# ETH_ICD_CCU_HAS.net
KiCad netlist of a schematic drawn in Altium Designer
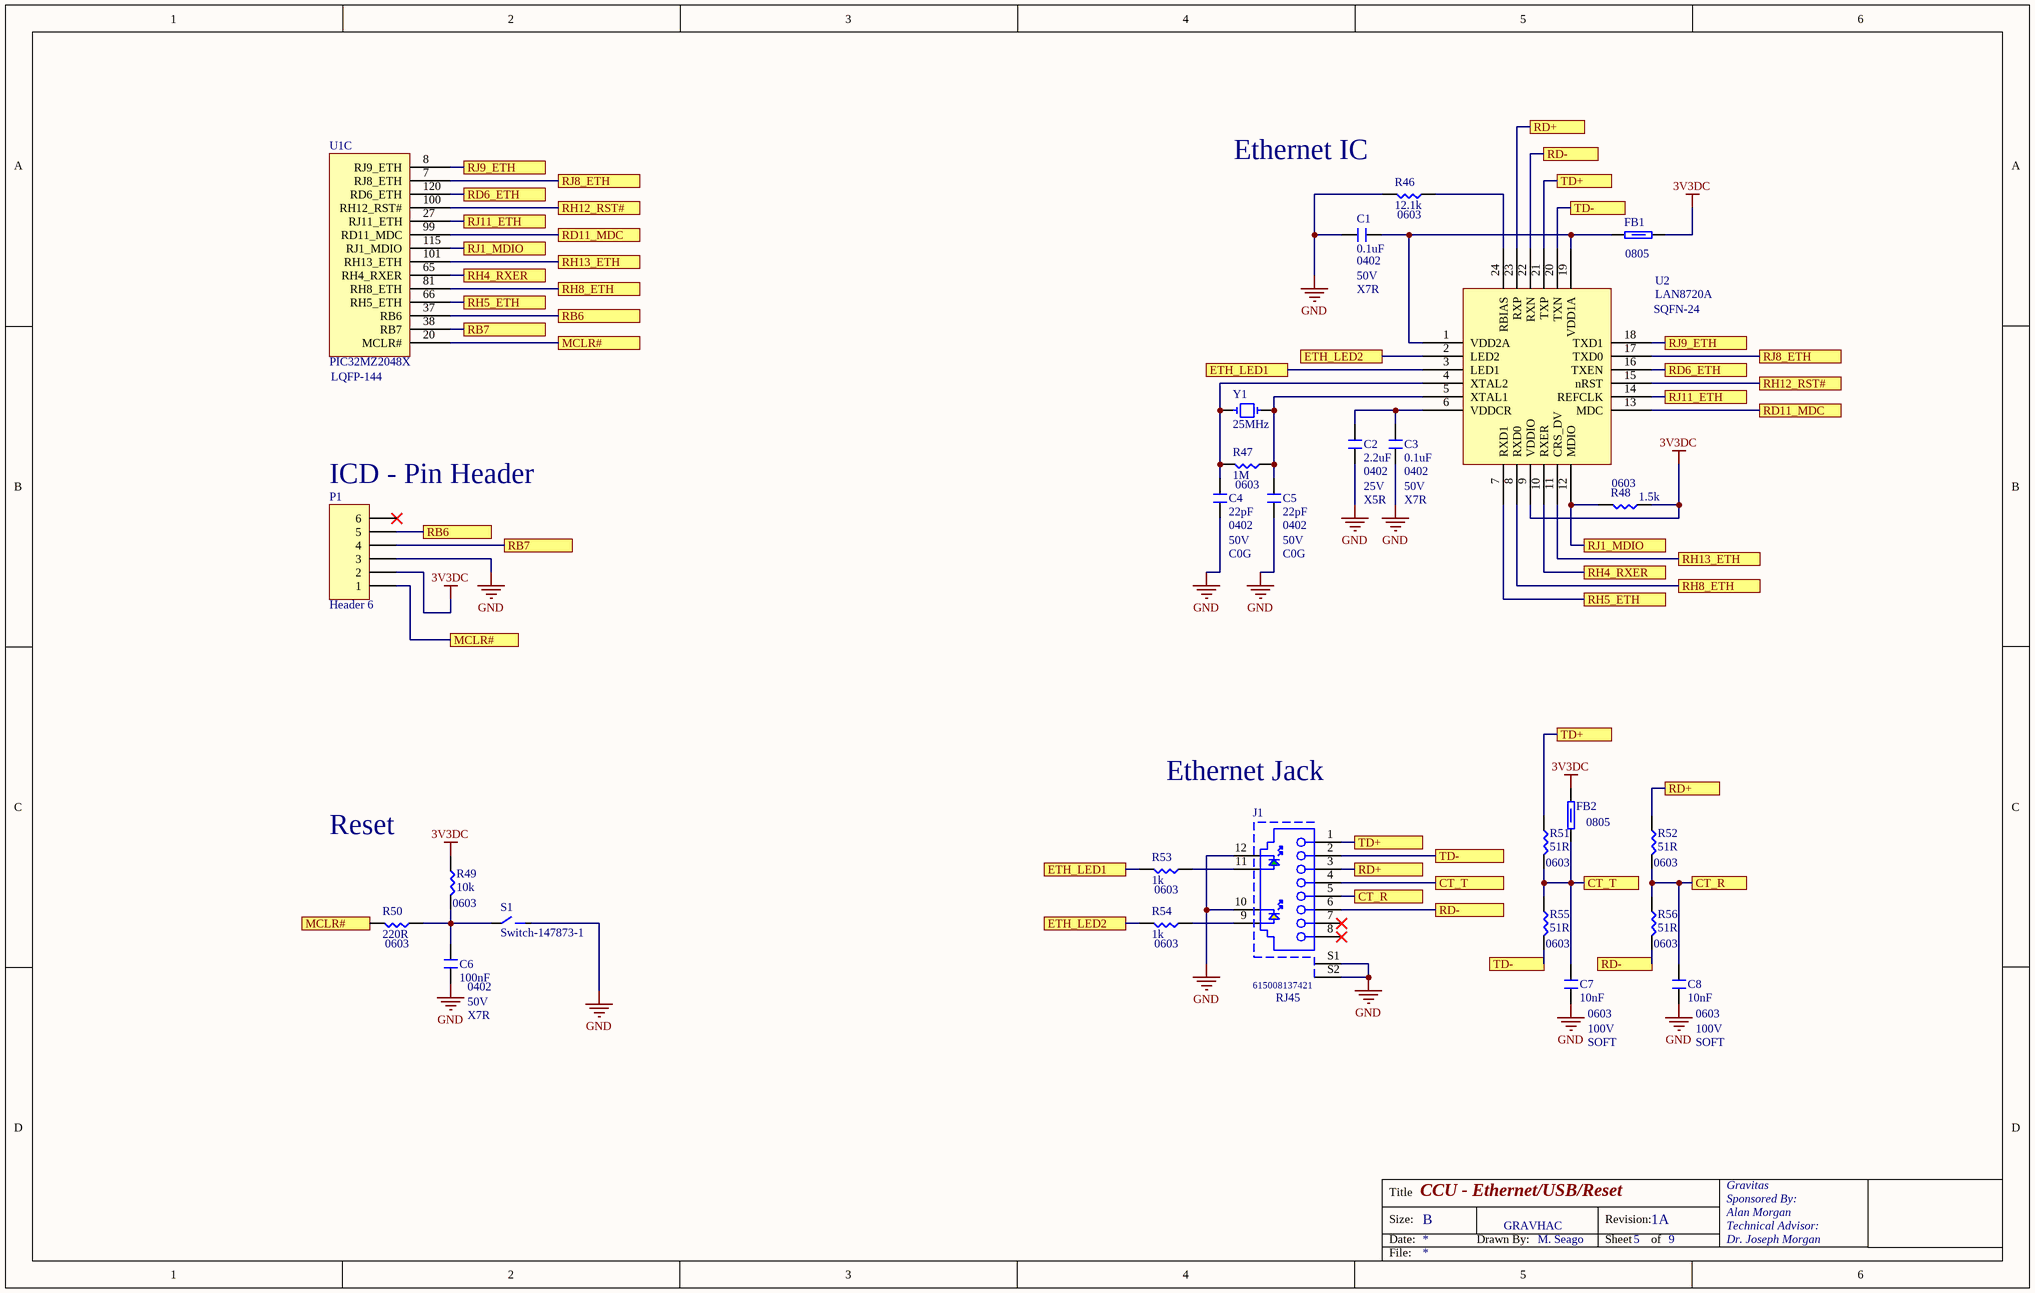
[diagram p0: ETH_ICD_CCU_HAS.SchDoc]

(export (version "E")
  (design (tool "Eeschema 10.0.6"))
  (components
    (comp (ref "C1")
      (value "0.1uF")
      (footprint "NonPolar-0402")
      (libsource (lib "GravLib") (part "Cap - 0402"))
    )
    (comp (ref "C2")
      (value "2.2uF")
      (footprint "NonPolar-0402")
      (libsource (lib "GravLib") (part "Cap - 0402"))
    )
    (comp (ref "C3")
      (value "0.1uF")
      (footprint "NonPolar-0402")
      (libsource (lib "GravLib") (part "Cap - 0402"))
    )
    (comp (ref "C4")
      (value "22pF")
      (footprint "NonPolar-0402")
      (libsource (lib "GravLib") (part "Cap - 0402"))
    )
    (comp (ref "C5")
      (value "22pF")
      (footprint "NonPolar-0402")
      (libsource (lib "GravLib") (part "Cap - 0402"))
    )
    (comp (ref "C6") (value "100nF") (footprint "NonPolar-0402") (libsource (lib "") (part "Cap - 0402_1")))
    (comp (ref "C7")
      (value "10nF")
      (footprint "NonPolar-0603")
      (libsource (lib "GravLib") (part "Cap - 0603"))
    )
    (comp (ref "C8")
      (value "10nF")
      (footprint "NonPolar-0603")
      (libsource (lib "GravLib") (part "Cap - 0603"))
    )
    (comp (ref "FB1")
      (value "Ferrite - 0805")
      (footprint "NonPolar-0805")
      (libsource (lib "GravLib") (part "Ferrite - 0805"))
    )
    (comp (ref "FB2")
      (value "Ferrite - 0805")
      (footprint "NonPolar-0805")
      (libsource (lib "GravLib") (part "Ferrite - 0805"))
    )
    (comp (ref "J1")
      (value "615008137421")
      (footprint "615008137421")
      (description "Modular Jack WR-MJ, Tab Up, Shielded, with LED and EMI Panel Finger, Horizontal Entry, THT, 8P8C")
      (fields (field (name "MANUFACTURER") "Wurth Elektronik") (field (name "PUBLISHER") "WurthElektronik"))
      (libsource (lib "Altium Content Vault") (part "WE-CN-1P-2F-J12_A"))
    )
    (comp (ref "P1")
      (value "Header 6")
      (footprint "HDR1X6")
      (description "Header, 6-Pin")
      (fields (field (name "PUBLISHER") "Altium Limited"))
      (libsource (lib "Miscellaneous Connectors") (part "Header 6"))
    )
    (comp (ref "R46")
      (value "12.1k")
      (footprint "NonPolar-0603")
      (libsource (lib "GravLib") (part "Res - 0603"))
    )
    (comp (ref "R47")
      (value "1M")
      (footprint "NonPolar-0603")
      (libsource (lib "GravLib") (part "Res - 0603"))
    )
    (comp (ref "R48")
      (value "1.5k")
      (footprint "NonPolar-0603")
      (libsource (lib "GravLib") (part "Res - 0603"))
    )
    (comp (ref "R49")
      (value "10k")
      (footprint "NonPolar-0603")
      (libsource (lib "GravLib") (part "Res - 0603"))
    )
    (comp (ref "R50")
      (value "220R")
      (footprint "NonPolar-0603")
      (libsource (lib "GravLib") (part "Res - 0603"))
    )
    (comp (ref "R51")
      (value "51R")
      (footprint "NonPolar-0603")
      (libsource (lib "GravLib") (part "Res - 0603"))
    )
    (comp (ref "R52")
      (value "51R")
      (footprint "NonPolar-0603")
      (libsource (lib "GravLib") (part "Res - 0603"))
    )
    (comp (ref "R53")
      (value "1k")
      (footprint "NonPolar-0603")
      (libsource (lib "GravLib") (part "Res - 0603"))
    )
    (comp (ref "R54")
      (value "1k")
      (footprint "NonPolar-0603")
      (libsource (lib "GravLib") (part "Res - 0603"))
    )
    (comp (ref "R55")
      (value "51R")
      (footprint "NonPolar-0603")
      (libsource (lib "GravLib") (part "Res - 0603"))
    )
    (comp (ref "R56")
      (value "51R")
      (footprint "NonPolar-0603")
      (libsource (lib "GravLib") (part "Res - 0603"))
    )
    (comp (ref "S1")
      (value "Switch-147873-1")
      (footprint "Switch - 147873-1")
      (libsource (lib "GravLib") (part "Switch-147873-1"))
    )
    (comp (ref "U1")
      (value "PIC32MZ2048X")
      (footprint "BIG_PIC32MZ")
      (libsource (lib "GravLib") (part "PIC32MZ2048X"))
    )
    (comp (ref "U2") (value "LAN8720A") (footprint "LAN8720A") (libsource (lib "GravLib") (part "LAN8720A")))
    (comp (ref "Y1")
      (value "25MHz")
      (footprint "7A-25.000MAAJ-T")
      (libsource (lib "GravLib") (part "25MHz -7A-25.000MAAJ-T"))
    )
  )
  (nets
    (net (code "1") (name "/CT_R") (class "Default")
      (node (ref "C8") (pin "2") (pinfunction "2_2") (pintype "passive"))
      (node (ref "J1") (pin "5") (pinfunction "5_5") (pintype "passive"))
      (node (ref "R52") (pin "1") (pinfunction "1_1") (pintype "passive"))
      (node (ref "R56") (pin "2") (pinfunction "2_2") (pintype "passive"))
    )
    (net (code "2") (name "/CT_T") (class "Default")
      (node (ref "C7") (pin "2") (pinfunction "2_2") (pintype "passive"))
      (node (ref "FB2") (pin "1") (pinfunction "1_1") (pintype "passive"))
      (node (ref "J1") (pin "4") (pinfunction "4_4") (pintype "passive"))
      (node (ref "R51") (pin "1") (pinfunction "1_1") (pintype "passive"))
      (node (ref "R55") (pin "2") (pinfunction "2_2") (pintype "passive"))
    )
    (net (code "3") (name "/ETH_LED1") (class "Default")
      (node (ref "R53") (pin "1") (pinfunction "1_1") (pintype "passive"))
      (node (ref "U2") (pin "3") (pinfunction "LED1_3") (pintype "passive"))
    )
    (net (code "4") (name "/ETH_LED2") (class "Default")
      (node (ref "R54") (pin "1") (pinfunction "1_1") (pintype "passive"))
      (node (ref "U2") (pin "2") (pinfunction "LED2_2") (pintype "passive"))
    )
    (net (code "5") (name "/MCLR#") (class "Default")
      (node (ref "P1") (pin "1") (pinfunction "1_1") (pintype "passive"))
      (node (ref "R50") (pin "1") (pinfunction "1_1") (pintype "passive"))
      (node (ref "U1") (pin "20") (pinfunction "MCLR#_20") (pintype "passive"))
    )
    (net (code "6") (name "/RB6") (class "Default")
      (node (ref "P1") (pin "5") (pinfunction "5_5") (pintype "passive"))
      (node (ref "U1") (pin "37") (pinfunction "RB6_37") (pintype "passive"))
    )
    (net (code "7") (name "/RB7") (class "Default")
      (node (ref "P1") (pin "4") (pinfunction "4_4") (pintype "passive"))
      (node (ref "U1") (pin "38") (pinfunction "RB7_38") (pintype "passive"))
    )
    (net (code "8") (name "/RD+") (class "Default")
      (node (ref "J1") (pin "3") (pinfunction "3_3") (pintype "passive"))
      (node (ref "R52") (pin "2") (pinfunction "2_2") (pintype "passive"))
      (node (ref "U2") (pin "23") (pinfunction "RXP_23") (pintype "passive"))
    )
    (net (code "9") (name "/RD-") (class "Default")
      (node (ref "J1") (pin "6") (pinfunction "6_6") (pintype "passive"))
      (node (ref "R56") (pin "1") (pinfunction "1_1") (pintype "passive"))
      (node (ref "U2") (pin "22") (pinfunction "RXN_22") (pintype "passive"))
    )
    (net (code "10") (name "/RD6_ETH") (class "Default")
      (node (ref "U1") (pin "120") (pinfunction "RD6_ETH_120") (pintype "passive"))
      (node (ref "U2") (pin "16") (pinfunction "TXEN_16") (pintype "passive"))
    )
    (net (code "11") (name "/RD11_MDC") (class "Default")
      (node (ref "U1") (pin "99") (pinfunction "RD11_MDC_99") (pintype "passive"))
      (node (ref "U2") (pin "13") (pinfunction "MDC_13") (pintype "passive"))
    )
    (net (code "12") (name "/RH4_RXER") (class "Default")
      (node (ref "U1") (pin "65") (pinfunction "RH4_RXER_65") (pintype "passive"))
      (node (ref "U2") (pin "10") (pinfunction "RXER_10") (pintype "passive"))
    )
    (net (code "13") (name "/RH5_ETH") (class "Default")
      (node (ref "U1") (pin "66") (pinfunction "RH5_ETH_66") (pintype "passive"))
      (node (ref "U2") (pin "7") (pinfunction "RXD1_7") (pintype "passive"))
    )
    (net (code "14") (name "/RH8_ETH") (class "Default")
      (node (ref "U1") (pin "81") (pinfunction "RH8_ETH_81") (pintype "passive"))
      (node (ref "U2") (pin "8") (pinfunction "RXD0_8") (pintype "passive"))
    )
    (net (code "15") (name "/RH12_RST#") (class "Default")
      (node (ref "U1") (pin "100") (pinfunction "RH12_RST#_100") (pintype "passive"))
      (node (ref "U2") (pin "15") (pinfunction "nRST_15") (pintype "passive"))
    )
    (net (code "16") (name "/RH13_ETH") (class "Default")
      (node (ref "U1") (pin "101") (pinfunction "RH13_ETH_101") (pintype "passive"))
      (node (ref "U2") (pin "11") (pinfunction "CRS_DV_11") (pintype "passive"))
    )
    (net (code "17") (name "/RJ1_MDIO") (class "Default")
      (node (ref "R48") (pin "1") (pinfunction "1_1") (pintype "passive"))
      (node (ref "U1") (pin "115") (pinfunction "RJ1_MDIO_115") (pintype "passive"))
      (node (ref "U2") (pin "12") (pinfunction "MDIO_12") (pintype "passive"))
    )
    (net (code "18") (name "/RJ8_ETH") (class "Default")
      (node (ref "U1") (pin "7") (pinfunction "RJ8_ETH_7") (pintype "passive"))
      (node (ref "U2") (pin "17") (pinfunction "TXD0_17") (pintype "passive"))
    )
    (net (code "19") (name "/RJ9_ETH") (class "Default")
      (node (ref "U1") (pin "8") (pinfunction "RJ9_ETH_8") (pintype "passive"))
      (node (ref "U2") (pin "18") (pinfunction "TXD1_18") (pintype "passive"))
    )
    (net (code "20") (name "/RJ11_ETH") (class "Default")
      (node (ref "U1") (pin "27") (pinfunction "RJ11_ETH_27") (pintype "passive"))
      (node (ref "U2") (pin "14") (pinfunction "REFCLK_14") (pintype "passive"))
    )
    (net (code "21") (name "/TD+") (class "Default")
      (node (ref "J1") (pin "1") (pinfunction "1_1") (pintype "passive"))
      (node (ref "R51") (pin "2") (pinfunction "2_2") (pintype "passive"))
      (node (ref "U2") (pin "21") (pinfunction "TXP_21") (pintype "passive"))
    )
    (net (code "22") (name "/TD-") (class "Default")
      (node (ref "J1") (pin "2") (pinfunction "2_2") (pintype "passive"))
      (node (ref "R55") (pin "1") (pinfunction "1_1") (pintype "passive"))
      (node (ref "U2") (pin "20") (pinfunction "TXN_20") (pintype "passive"))
    )
    (net (code "23") (name "3V3DC") (class "Default")
      (node (ref "FB1") (pin "2") (pinfunction "2_2") (pintype "passive"))
      (node (ref "FB2") (pin "2") (pinfunction "2_2") (pintype "passive"))
      (node (ref "P1") (pin "2") (pinfunction "2_2") (pintype "passive"))
      (node (ref "R48") (pin "2") (pinfunction "2_2") (pintype "passive"))
      (node (ref "R49") (pin "2") (pinfunction "2_2") (pintype "passive"))
      (node (ref "U2") (pin "9") (pinfunction "VDDIO_9") (pintype "passive"))
    )
    (net (code "24") (name "GND") (class "Default")
      (node (ref "C1") (pin "1") (pinfunction "1_1") (pintype "passive"))
      (node (ref "C2") (pin "1") (pinfunction "1_1") (pintype "passive"))
      (node (ref "C3") (pin "1") (pinfunction "1_1") (pintype "passive"))
      (node (ref "C4") (pin "1") (pinfunction "1_1") (pintype "passive"))
      (node (ref "C5") (pin "1") (pinfunction "1_1") (pintype "passive"))
      (node (ref "C6") (pin "1") (pinfunction "1_1") (pintype "passive"))
      (node (ref "C7") (pin "1") (pinfunction "1_1") (pintype "passive"))
      (node (ref "C8") (pin "1") (pinfunction "1_1") (pintype "passive"))
      (node (ref "J1") (pin "10") (pinfunction "10_10") (pintype "passive"))
      (node (ref "J1") (pin "12") (pinfunction "12_12") (pintype "passive"))
      (node (ref "J1") (pin "S1") (pinfunction "S1_S1") (pintype "passive"))
      (node (ref "J1") (pin "S2") (pinfunction "S2_S2") (pintype "passive"))
      (node (ref "P1") (pin "3") (pinfunction "3_3") (pintype "passive"))
      (node (ref "R46") (pin "1") (pinfunction "1_1") (pintype "passive"))
      (node (ref "S1") (pin "2") (pinfunction "2_2") (pintype "passive"))
    )
    (net (code "25") (name "Net-(C6-Pad2)") (class "Default")
      (node (ref "C6") (pin "2") (pinfunction "2_2") (pintype "passive"))
      (node (ref "R49") (pin "1") (pinfunction "1_1") (pintype "passive"))
      (node (ref "R50") (pin "2") (pinfunction "2_2") (pintype "passive"))
      (node (ref "S1") (pin "1") (pinfunction "1_1") (pintype "passive"))
    )
    (net (code "26") (name "Net-(J1-Pad9)") (class "Default")
      (node (ref "J1") (pin "9") (pinfunction "9_9") (pintype "passive"))
      (node (ref "R54") (pin "2") (pinfunction "2_2") (pintype "passive"))
    )
    (net (code "27") (name "Net-(J1-Pad11)") (class "Default")
      (node (ref "J1") (pin "11") (pinfunction "11_11") (pintype "passive"))
      (node (ref "R53") (pin "2") (pinfunction "2_2") (pintype "passive"))
    )
    (net (code "28") (name "Net-(U2-RBIAS)") (class "Default")
      (node (ref "R46") (pin "2") (pinfunction "2_2") (pintype "passive"))
      (node (ref "U2") (pin "24") (pinfunction "RBIAS_24") (pintype "passive"))
    )
    (net (code "29") (name "Net-(U2-VDD1A)") (class "Default")
      (node (ref "C1") (pin "2") (pinfunction "2_2") (pintype "passive"))
      (node (ref "FB1") (pin "1") (pinfunction "1_1") (pintype "passive"))
      (node (ref "U2") (pin "1") (pinfunction "VDD2A_1") (pintype "passive"))
      (node (ref "U2") (pin "19") (pinfunction "VDD1A_19") (pintype "passive"))
    )
    (net (code "30") (name "Net-(U2-VDDCR)") (class "Default")
      (node (ref "C2") (pin "2") (pinfunction "2_2") (pintype "passive"))
      (node (ref "C3") (pin "2") (pinfunction "2_2") (pintype "passive"))
      (node (ref "U2") (pin "6") (pinfunction "VDDCR_6") (pintype "passive"))
    )
    (net (code "31") (name "Net-(U2-XTAL1)") (class "Default")
      (node (ref "C5") (pin "2") (pinfunction "2_2") (pintype "passive"))
      (node (ref "R47") (pin "2") (pinfunction "2_2") (pintype "passive"))
      (node (ref "U2") (pin "5") (pinfunction "XTAL1_5") (pintype "passive"))
      (node (ref "Y1") (pin "2") (pinfunction "2_2") (pintype "passive"))
    )
    (net (code "32") (name "Net-(U2-XTAL2)") (class "Default")
      (node (ref "C4") (pin "2") (pinfunction "2_2") (pintype "passive"))
      (node (ref "R47") (pin "1") (pinfunction "1_1") (pintype "passive"))
      (node (ref "U2") (pin "4") (pinfunction "XTAL2_4") (pintype "passive"))
      (node (ref "Y1") (pin "1") (pinfunction "1_1") (pintype "passive"))
    )
    (net (code "33") (name "unconnected-(J1-Pad7)") (class "Default")
      (node (ref "J1") (pin "7") (pinfunction "7_7") (pintype "passive+no_connect"))
    )
    (net (code "34") (name "unconnected-(J1-Pad8)") (class "Default")
      (node (ref "J1") (pin "8") (pinfunction "8_8") (pintype "passive+no_connect"))
    )
    (net (code "35") (name "unconnected-(P1-Pad6)") (class "Default")
      (node (ref "P1") (pin "6") (pinfunction "6_6") (pintype "passive+no_connect"))
    )
  )
)
